# DC27-bottom.net
KiCad netlist of a schematic drawn in EAGLE
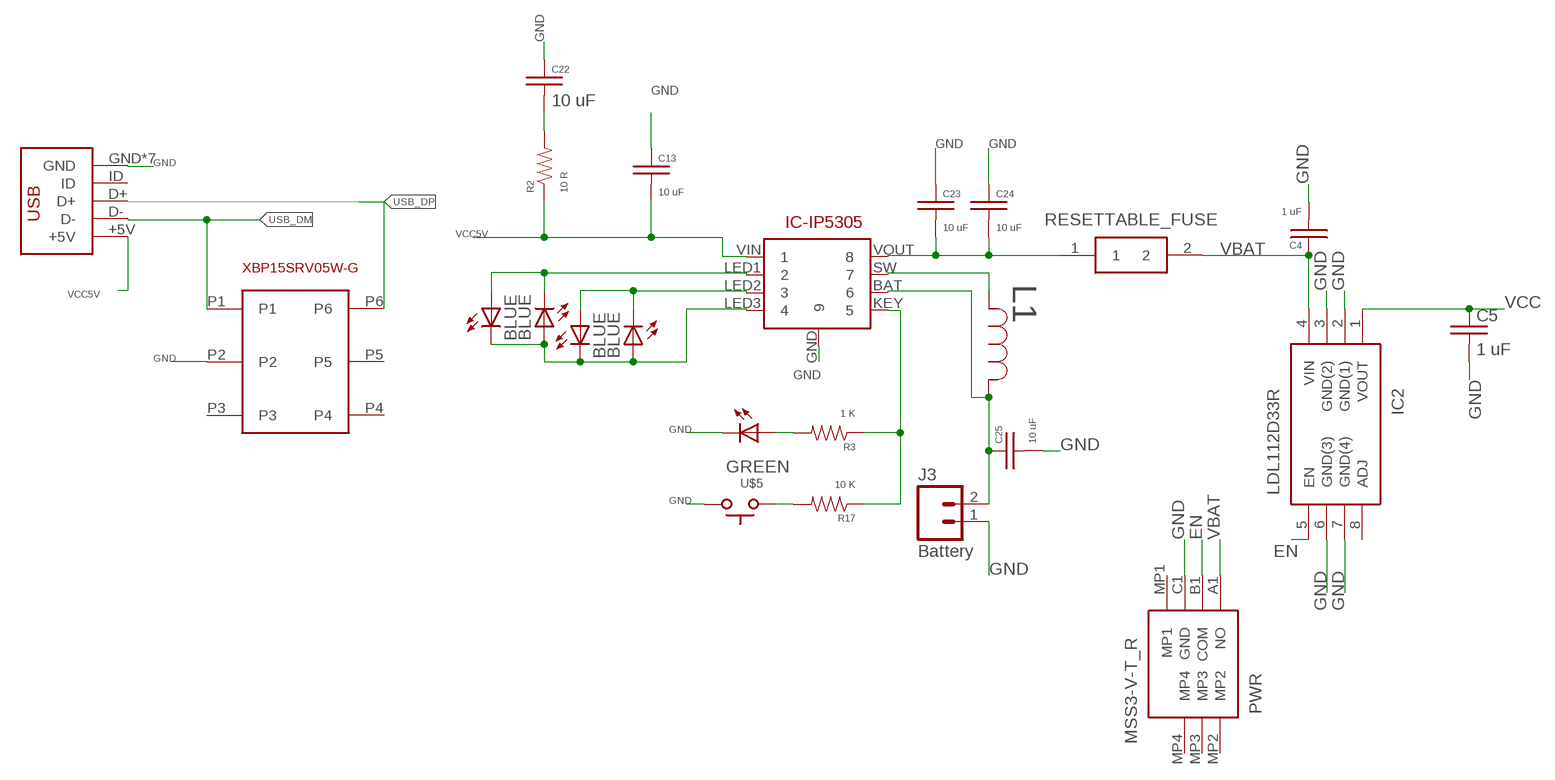
[diagram p0: schematic, sheet 1]
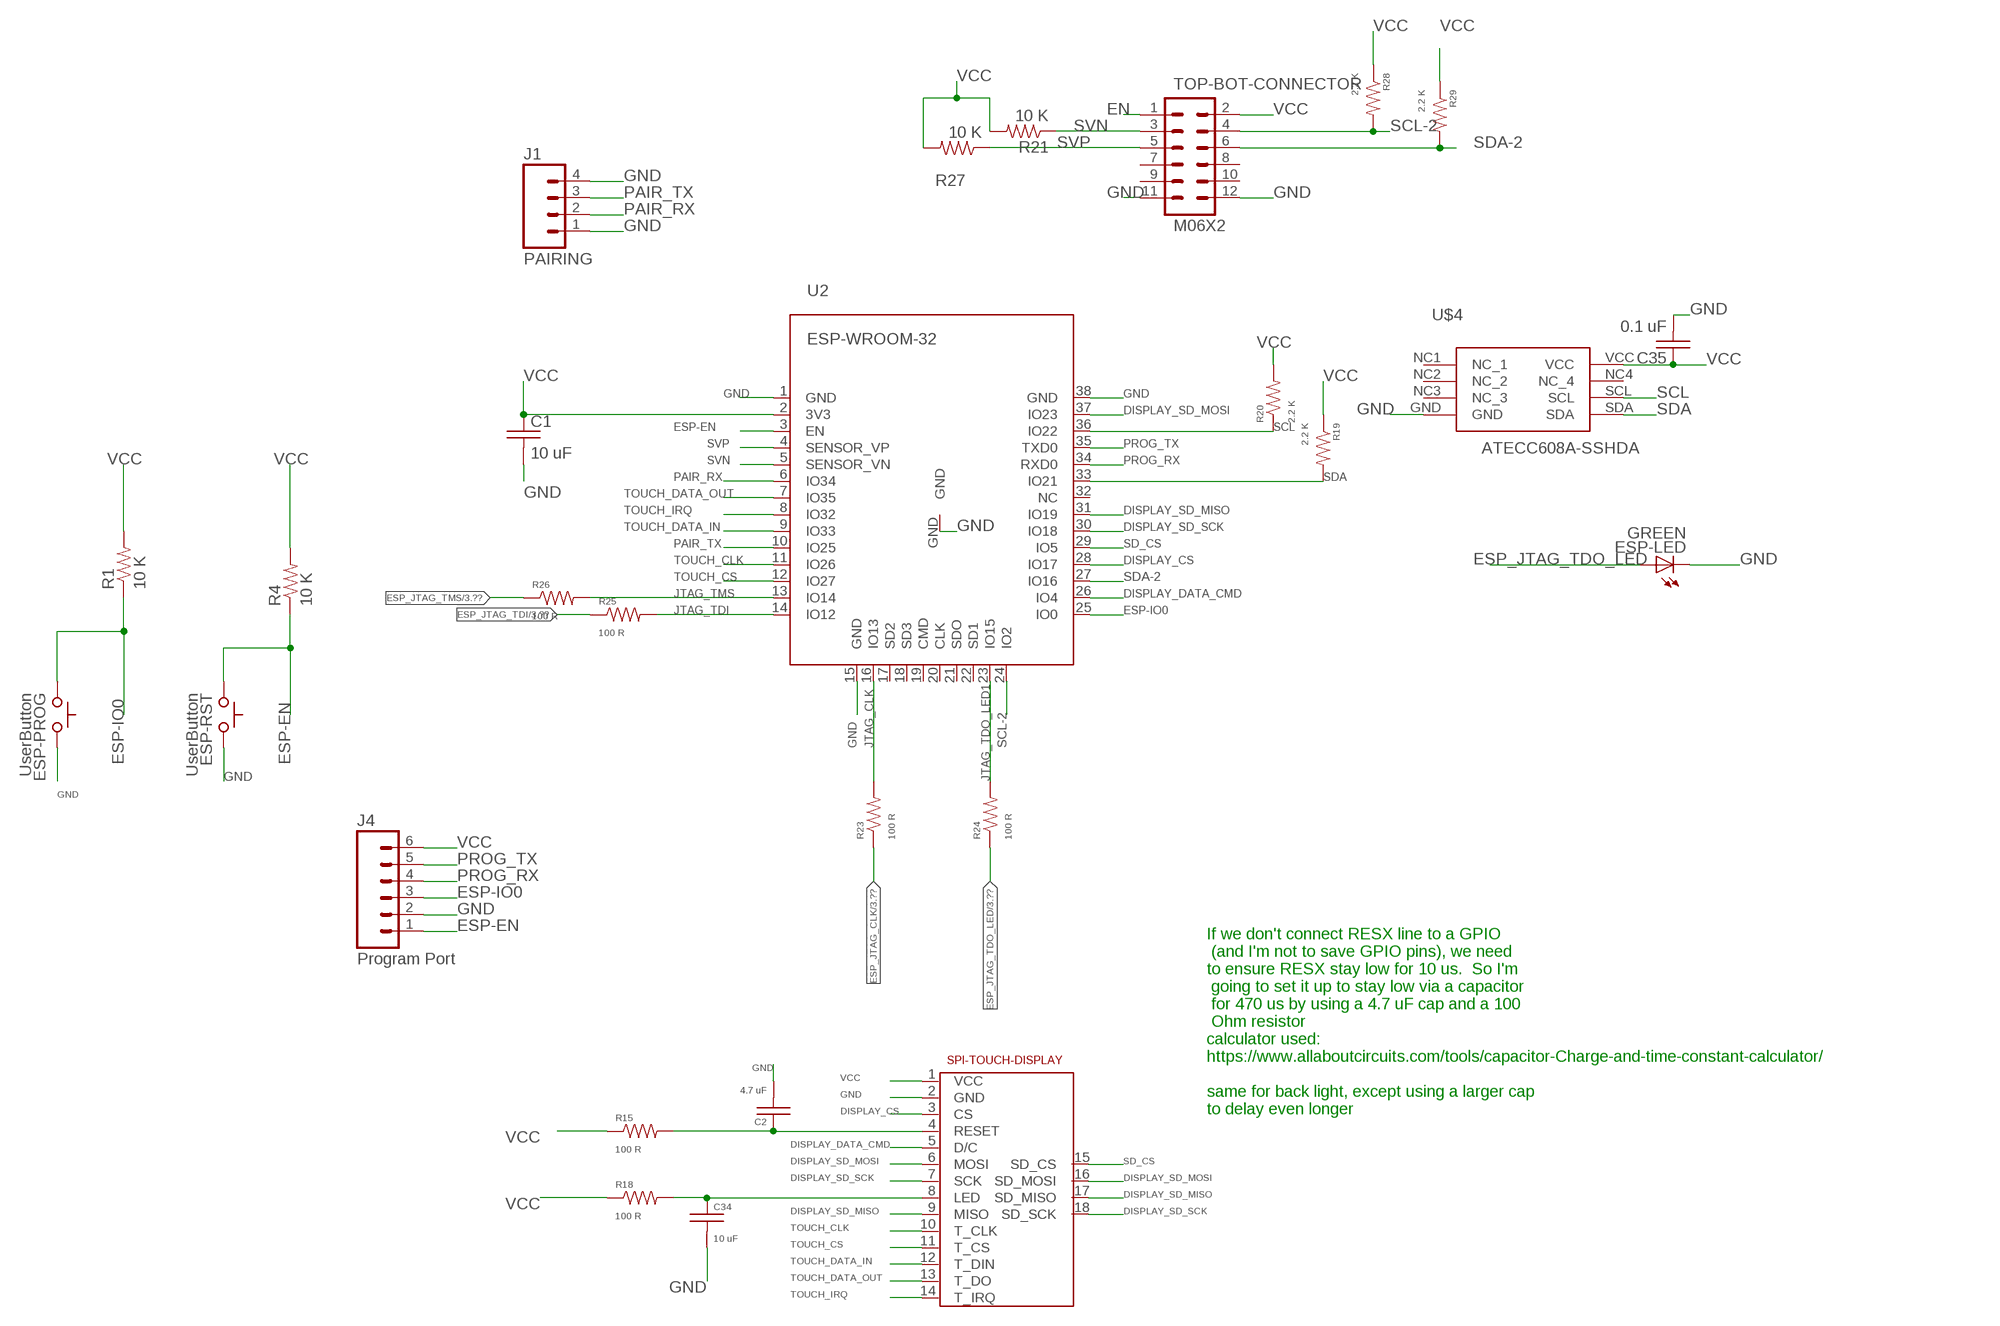
[diagram p1: schematic, sheet 2]
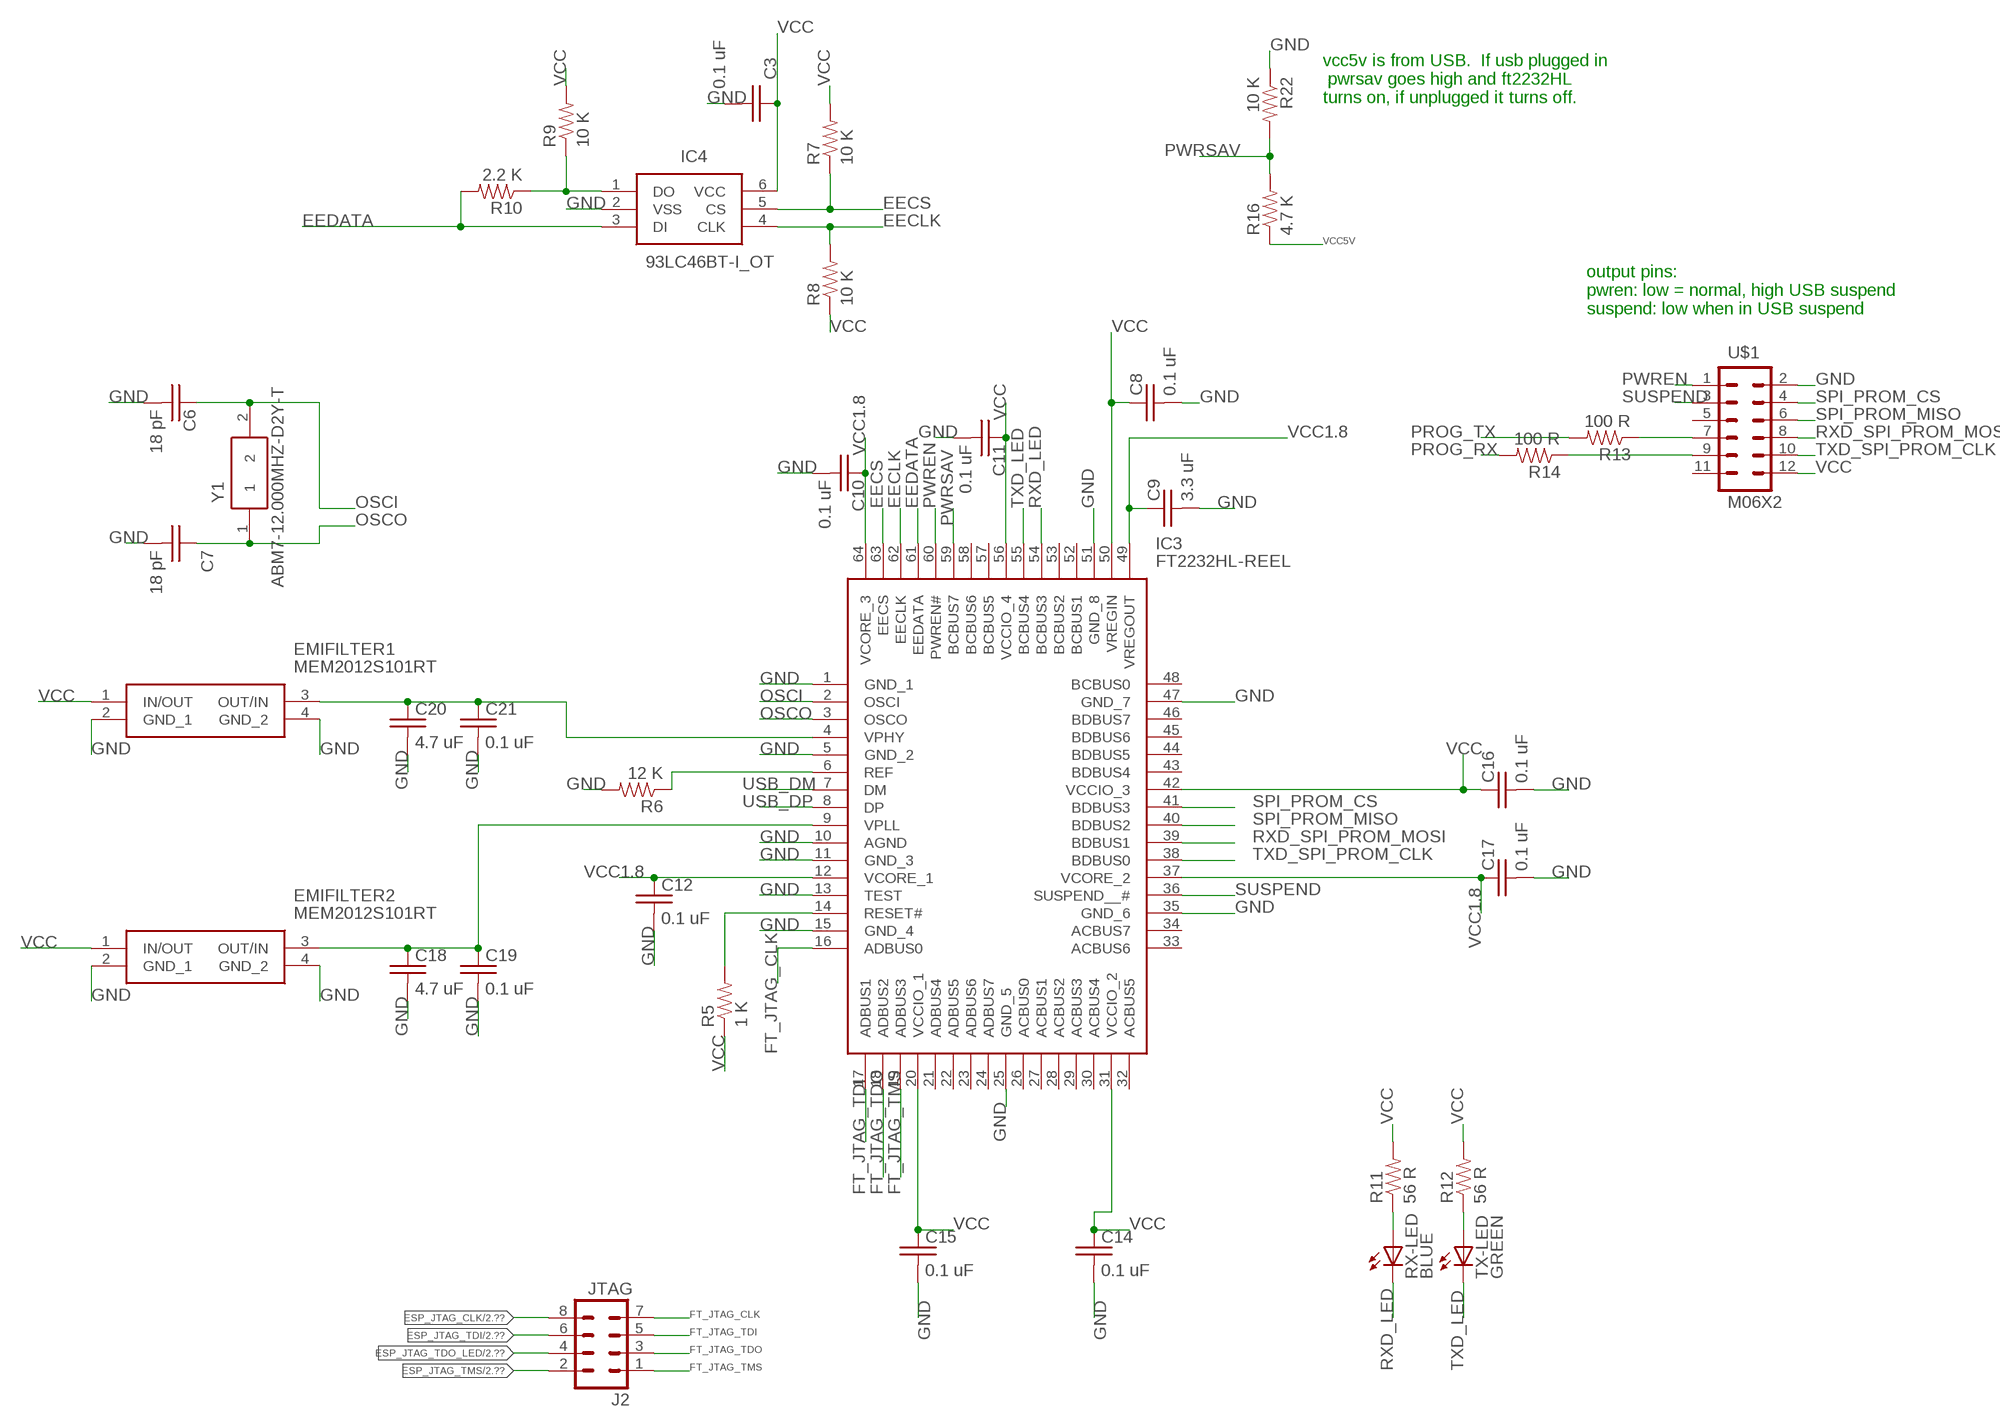
[diagram p2: schematic, sheet 3]
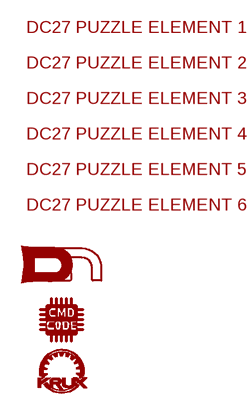
[diagram p3: schematic, sheet 4]

(export (version "E")
  (design (tool "Eeschema 10.0.6"))
  (components
    (comp (ref "C4")
      (value "1 uF")
      (footprint "eagle-import:C0805")
      (libsource (lib "eagle-import") (part "C-USC0805"))
    )
    (comp (ref "C5")
      (value "1 uF")
      (footprint "eagle-import:C0805")
      (libsource (lib "eagle-import") (part "C-USC0805"))
    )
    (comp (ref "C13")
      (value "10 uF")
      (footprint "eagle-import:C0805")
      (libsource (lib "eagle-import") (part "C-USC0805"))
    )
    (comp (ref "C22")
      (value "10 uF")
      (footprint "eagle-import:C0805")
      (libsource (lib "eagle-import") (part "C-USC0805"))
    )
    (comp (ref "C23")
      (value "10 uF")
      (footprint "eagle-import:C0805")
      (libsource (lib "eagle-import") (part "C-USC0805"))
    )
    (comp (ref "C24")
      (value "10 uF")
      (footprint "eagle-import:C0805")
      (libsource (lib "eagle-import") (part "C-USC0805"))
    )
    (comp (ref "C25")
      (value "10 uF")
      (footprint "eagle-import:C0805")
      (libsource (lib "eagle-import") (part "C-USC0805"))
    )
    (comp (ref "CL1")
      (value "BLUE")
      (footprint "eagle-import:LED-1206")
      (libsource (lib "eagle-import") (part "LED1206"))
    )
    (comp (ref "CL2")
      (value "BLUE")
      (footprint "eagle-import:LED-1206")
      (libsource (lib "eagle-import") (part "LED1206"))
    )
    (comp (ref "CL3")
      (value "BLUE")
      (footprint "eagle-import:LED-1206")
      (libsource (lib "eagle-import") (part "LED1206"))
    )
    (comp (ref "CL4")
      (value "BLUE")
      (footprint "eagle-import:LED-1206")
      (libsource (lib "eagle-import") (part "LED1206"))
    )
    (comp (ref "IC-IP5305")
      (value "IP5305ESOP8")
      (footprint "eagle-import:SOIC127P600X165-8")
      (libsource (lib "eagle-import") (part "IP5305ESOP8"))
    )
    (comp (ref "IC2")
      (value "LDL112D33R")
      (footprint "eagle-import:SOIC127P600X175-8N")
      (libsource (lib "eagle-import") (part "LDL112D33R"))
    )
    (comp (ref "J3")
      (value "Battery")
      (footprint "eagle-import:JST-2-PTH")
      (libsource (lib "eagle-import") (part "M02JST-PTH-2"))
    )
    (comp (ref "KEYLED")
      (value "GREEN")
      (footprint "eagle-import:LED-1206")
      (libsource (lib "eagle-import") (part "LED1206"))
    )
    (comp (ref "L1")
      (value "2.2uH")
      (footprint "eagle-import:IND_TAIYO_NRS4018")
      (fields (field (name "MANUFACTURER_PART_NUMBER") "NRS4018T2R2MDGJ"))
      (libsource (lib "eagle-import") (part "NRS4018T2R2MDGJ"))
    )
    (comp (ref "PWR")
      (value "MSS3-V-T_R")
      (footprint "eagle-import:MSS3VTR")
      (fields
        (field (name "MANUFACTURER_PART_NUMBER") "MSS3-V-T/R")
        (field (name "MOUSER_PART_NUMBER") "113-MSS3-V-T/R")
      )
      (libsource (lib "eagle-import") (part "MSS3-V-T_R"))
    )
    (comp (ref "R2")
      (value "10 R")
      (footprint "eagle-import:0805")
      (libsource (lib "eagle-import") (part "passives_RESISTOR0805-RES"))
    )
    (comp (ref "R3")
      (value "1 K")
      (footprint "eagle-import:0805")
      (libsource (lib "eagle-import") (part "passives_RESISTOR0805-RES"))
    )
    (comp (ref "R17")
      (value "10 K")
      (footprint "eagle-import:0805")
      (libsource (lib "eagle-import") (part "passives_RESISTOR0805-RES"))
    )
    (comp (ref "RESETTABLE_FUSE")
      (value "0ZCJ0050FF2G")
      (footprint "eagle-import:FUSC3216X55N")
      (libsource (lib "eagle-import") (part "0ZCJ0050FF2G"))
    )
    (comp (ref "U$2")
      (value "XBP15SRV05W-G")
      (footprint "eagle-import:SOT-26P-XBP15SRV05W-G")
      (fields (field (name "DIGI_KEY_PART_NUMBER") "893-1422-1-ND"))
      (libsource (lib "eagle-import") (part "XBP15SRV05W-G"))
    )
    (comp (ref "U$3")
      (value "DX4R005JJ2DX4R005JJ2")
      (footprint "eagle-import:DX4R005JJ2")
      (libsource (lib "eagle-import") (part "DX4R005JJ2DX4R005JJ2"))
    )
    (comp (ref "U$5")
      (value "SWITCH_TACTILETACTILE-2PIN-NARROW")
      (footprint "eagle-import:TACTILE-2PIN-NARROW")
      (libsource (lib "eagle-import") (part "switches_SWITCH_TACTILETACTILE-2PIN-NARROW"))
    )
    (comp (ref "U$6")
      (value "DC27_PUZZLE_ELEMENT_1")
      (footprint "eagle-import:DC27_PUZZLE_ELEMENT_1")
      (libsource (lib "eagle-import") (part "DC27_PUZZLE_ELEMENT_1"))
    )
    (comp (ref "U$7")
      (value "KRUX_LOGO")
      (footprint "eagle-import:KRUX_LOGO")
      (libsource (lib "eagle-import") (part "KRUX_LOGO"))
    )
    (comp (ref "U$8")
      (value "CMD_C0DE_LOGO")
      (footprint "eagle-import:CMD_C0DE_LOGO")
      (libsource (lib "eagle-import") (part "CMD_C0DE_LOGO"))
    )
    (comp (ref "U$9")
      (value "DN_LOGODC26")
      (footprint "eagle-import:DN_LOGO_DC26")
      (libsource (lib "eagle-import") (part "DN_LOGODC26"))
    )
    (comp (ref "U$11")
      (value "DC27_PUZZLE_ELEMENT_2")
      (footprint "eagle-import:DC27_PUZZLE_ELEMENT_2")
      (libsource (lib "eagle-import") (part "DC27_PUZZLE_ELEMENT_2"))
    )
    (comp (ref "U$12")
      (value "DC27_PUZZLE_ELEMENT_3")
      (footprint "eagle-import:DC27_PUZZLE_ELEMENT_3")
      (libsource (lib "eagle-import") (part "DC27_PUZZLE_ELEMENT_3"))
    )
    (comp (ref "U$13")
      (value "DC27_PUZZLE_ELEMENT_4")
      (footprint "eagle-import:DC27_PUZZLE_ELEMENT_4")
      (libsource (lib "eagle-import") (part "DC27_PUZZLE_ELEMENT_4"))
    )
    (comp (ref "U$14")
      (value "DC27_PUZZLE_ELEMENT_5")
      (footprint "eagle-import:DC27_PUZZLE_ELEMENT_5")
      (libsource (lib "eagle-import") (part "DC27_PUZZLE_ELEMENT_5"))
    )
    (comp (ref "U$15")
      (value "DC27_PUZZLE_ELEMENT_6")
      (footprint "eagle-import:DC27_PUZZLE_ELEMENT_6")
      (libsource (lib "eagle-import") (part "DC27_PUZZLE_ELEMENT_6"))
    )
    (comp (ref "C3")
      (value "0.1 uF")
      (footprint "eagle-import:C0805")
      (libsource (lib "eagle-import") (part "C-USC0805"))
    )
    (comp (ref "C6")
      (value "18 pF")
      (footprint "eagle-import:C0805")
      (libsource (lib "eagle-import") (part "C-USC0805"))
    )
    (comp (ref "C7")
      (value "18 pF")
      (footprint "eagle-import:C0805")
      (libsource (lib "eagle-import") (part "C-USC0805"))
    )
    (comp (ref "C8")
      (value "0.1 uF")
      (footprint "eagle-import:C0805")
      (libsource (lib "eagle-import") (part "C-USC0805"))
    )
    (comp (ref "C9")
      (value "3.3 uF")
      (footprint "eagle-import:C0805")
      (libsource (lib "eagle-import") (part "C-USC0805"))
    )
    (comp (ref "C10")
      (value "0.1 uF")
      (footprint "eagle-import:C0805")
      (libsource (lib "eagle-import") (part "C-USC0805"))
    )
    (comp (ref "C11")
      (value "0.1 uF")
      (footprint "eagle-import:C0805")
      (libsource (lib "eagle-import") (part "C-USC0805"))
    )
    (comp (ref "C12")
      (value "0.1 uF")
      (footprint "eagle-import:C0805")
      (libsource (lib "eagle-import") (part "C-USC0805"))
    )
    (comp (ref "C14")
      (value "0.1 uF")
      (footprint "eagle-import:C0805")
      (libsource (lib "eagle-import") (part "C-USC0805"))
    )
    (comp (ref "C15")
      (value "0.1 uF")
      (footprint "eagle-import:C0805")
      (libsource (lib "eagle-import") (part "C-USC0805"))
    )
    (comp (ref "C16")
      (value "0.1 uF")
      (footprint "eagle-import:C0805")
      (libsource (lib "eagle-import") (part "C-USC0805"))
    )
    (comp (ref "C17")
      (value "0.1 uF")
      (footprint "eagle-import:C0805")
      (libsource (lib "eagle-import") (part "C-USC0805"))
    )
    (comp (ref "C18")
      (value "4.7 uF")
      (footprint "eagle-import:C0805")
      (libsource (lib "eagle-import") (part "C-USC0805"))
    )
    (comp (ref "C19")
      (value "0.1 uF")
      (footprint "eagle-import:C0805")
      (libsource (lib "eagle-import") (part "C-USC0805"))
    )
    (comp (ref "C20")
      (value "4.7 uF")
      (footprint "eagle-import:C0805")
      (libsource (lib "eagle-import") (part "C-USC0805"))
    )
    (comp (ref "C21")
      (value "0.1 uF")
      (footprint "eagle-import:C0805")
      (libsource (lib "eagle-import") (part "C-USC0805"))
    )
    (comp (ref "EMIFILTER1")
      (value "MEM2012S101RT")
      (footprint "eagle-import:MEM2012S101RT")
      (libsource (lib "eagle-import") (part "MEM2012S101RT"))
    )
    (comp (ref "EMIFILTER2")
      (value "MEM2012S101RT")
      (footprint "eagle-import:MEM2012S101RT")
      (libsource (lib "eagle-import") (part "MEM2012S101RT"))
    )
    (comp (ref "IC3")
      (value "FT2232HL-REEL")
      (footprint "eagle-import:QFP50P1200X1200X160-64N")
      (fields (field (name "MOUSER_PART_NUMBER") "895-FT2232HL"))
      (libsource (lib "eagle-import") (part "FT2232HL-REEL"))
    )
    (comp (ref "IC4")
      (value "93LC46BT-I_OT")
      (footprint "eagle-import:SOT95P270X145-6N")
      (fields
        (field (name "MANUFACTURER_PART_NUMBER") "93LC46BT-I/OT")
        (field (name "MOUSER_PART_NUMBER") "579-93LC46BT-I/OT")
      )
      (libsource (lib "eagle-import") (part "93LC46BT-I_OT"))
    )
    (comp (ref "J2")
      (value "JTAG")
      (footprint "eagle-import:2X4")
      (libsource (lib "eagle-import") (part "M04X2"))
    )
    (comp (ref "R5")
      (value "1 K")
      (footprint "eagle-import:0805")
      (libsource (lib "eagle-import") (part "passives_RESISTOR0805-RES"))
    )
    (comp (ref "R6")
      (value "12 K")
      (footprint "eagle-import:0805")
      (libsource (lib "eagle-import") (part "passives_RESISTOR0805-RES"))
    )
    (comp (ref "R7")
      (value "10 K")
      (footprint "eagle-import:0805")
      (libsource (lib "eagle-import") (part "passives_RESISTOR0805-RES"))
    )
    (comp (ref "R8")
      (value "10 K")
      (footprint "eagle-import:0805")
      (libsource (lib "eagle-import") (part "passives_RESISTOR0805-RES"))
    )
    (comp (ref "R9")
      (value "10 K")
      (footprint "eagle-import:0805")
      (libsource (lib "eagle-import") (part "passives_RESISTOR0805-RES"))
    )
    (comp (ref "R10")
      (value "2.2 K")
      (footprint "eagle-import:0805")
      (libsource (lib "eagle-import") (part "passives_RESISTOR0805-RES"))
    )
    (comp (ref "R11")
      (value "56 R")
      (footprint "eagle-import:0805")
      (libsource (lib "eagle-import") (part "passives_RESISTOR0805-RES"))
    )
    (comp (ref "R12")
      (value "56 R")
      (footprint "eagle-import:0805")
      (libsource (lib "eagle-import") (part "passives_RESISTOR0805-RES"))
    )
    (comp (ref "R13")
      (value "100 R")
      (footprint "eagle-import:0805")
      (libsource (lib "eagle-import") (part "passives_RESISTOR0805-RES"))
    )
    (comp (ref "R14")
      (value "100 R")
      (footprint "eagle-import:0805")
      (libsource (lib "eagle-import") (part "passives_RESISTOR0805-RES"))
    )
    (comp (ref "R16")
      (value "4.7 K")
      (footprint "eagle-import:0805")
      (libsource (lib "eagle-import") (part "passives_RESISTOR0805-RES"))
    )
    (comp (ref "R22")
      (value "10 K")
      (footprint "eagle-import:0805")
      (libsource (lib "eagle-import") (part "passives_RESISTOR0805-RES"))
    )
    (comp (ref "RX-LED")
      (value "BLUE")
      (footprint "eagle-import:LED-1206")
      (libsource (lib "eagle-import") (part "LED1206"))
    )
    (comp (ref "TX-LED")
      (value "GREEN")
      (footprint "eagle-import:LED-1206")
      (libsource (lib "eagle-import") (part "LED1206"))
    )
    (comp (ref "U$1")
      (value "M06X2")
      (footprint "eagle-import:2X6")
      (libsource (lib "eagle-import") (part "M06X2"))
    )
    (comp (ref "Y1")
      (value "ABM7-12.000MHZ-D2Y-T")
      (footprint "eagle-import:ABM7")
      (fields
        (field (name "MOUSER_PART_NUMBER") "815-ABM7-12-D2Y-T")
        (field (name "RS_PART_NUMBER") "1710625P")
      )
      (libsource (lib "eagle-import") (part "ABM7-12.000MHZ-D2Y-T"))
    )
    (comp (ref "C1")
      (value "10 uF")
      (footprint "eagle-import:C0805")
      (libsource (lib "eagle-import") (part "C-USC0805"))
    )
    (comp (ref "C2")
      (value "4.7 uF")
      (footprint "eagle-import:C0805")
      (libsource (lib "eagle-import") (part "C-USC0805"))
    )
    (comp (ref "C34")
      (value "10 uF")
      (footprint "eagle-import:C0805")
      (libsource (lib "eagle-import") (part "C-USC0805"))
    )
    (comp (ref "C35")
      (value "0.1 uF")
      (footprint "eagle-import:C0805")
      (libsource (lib "eagle-import") (part "C-USC0805"))
    )
    (comp (ref "ESP-LED")
      (value "GREEN")
      (footprint "eagle-import:LED-1206")
      (libsource (lib "eagle-import") (part "LED1206"))
    )
    (comp (ref "ESP-PROG")
      (value "UserButton")
      (footprint "eagle-import:TACTILE-2PIN-NARROW")
      (libsource (lib "eagle-import") (part "SWITCH_TACTILETACTILE-2PIN-NARROW"))
    )
    (comp (ref "ESP-RST")
      (value "UserButton")
      (footprint "eagle-import:TACTILE-2PIN-NARROW")
      (libsource (lib "eagle-import") (part "SWITCH_TACTILETACTILE-2PIN-NARROW"))
    )
    (comp (ref "J1")
      (value "PAIRING")
      (footprint "eagle-import:1X04")
      (libsource (lib "eagle-import") (part "M04PTH"))
    )
    (comp (ref "J4")
      (value "Program Port")
      (footprint "eagle-import:1X06-SMD-POGO")
      (libsource (lib "eagle-import") (part "M06POGO-PIN"))
    )
    (comp (ref "R1")
      (value "10 K")
      (footprint "eagle-import:0805")
      (libsource (lib "eagle-import") (part "RESISTOR0805-RES"))
    )
    (comp (ref "R4")
      (value "10 K")
      (footprint "eagle-import:0805")
      (libsource (lib "eagle-import") (part "RESISTOR0805-RES"))
    )
    (comp (ref "R15")
      (value "100 R")
      (footprint "eagle-import:0805")
      (libsource (lib "eagle-import") (part "RESISTOR0805-RES"))
    )
    (comp (ref "R18")
      (value "100 R")
      (footprint "eagle-import:0805")
      (libsource (lib "eagle-import") (part "RESISTOR0805-RES"))
    )
    (comp (ref "R19")
      (value "2.2 K")
      (footprint "eagle-import:0805")
      (libsource (lib "eagle-import") (part "RESISTOR0805-RES"))
    )
    (comp (ref "R20")
      (value "2.2 K")
      (footprint "eagle-import:0805")
      (libsource (lib "eagle-import") (part "RESISTOR0805-RES"))
    )
    (comp (ref "R21")
      (value "10 K")
      (footprint "eagle-import:0805")
      (libsource (lib "eagle-import") (part "RESISTOR0805-RES"))
    )
    (comp (ref "R23")
      (value "100 R")
      (footprint "eagle-import:0805")
      (libsource (lib "eagle-import") (part "RESISTOR0805-RES"))
    )
    (comp (ref "R24")
      (value "100 R")
      (footprint "eagle-import:0805")
      (libsource (lib "eagle-import") (part "RESISTOR0805-RES"))
    )
    (comp (ref "R25")
      (value "100 R")
      (footprint "eagle-import:0805")
      (libsource (lib "eagle-import") (part "RESISTOR0805-RES"))
    )
    (comp (ref "R26")
      (value "100 R")
      (footprint "eagle-import:0805")
      (libsource (lib "eagle-import") (part "RESISTOR0805-RES"))
    )
    (comp (ref "R27")
      (value "10 K")
      (footprint "eagle-import:0805")
      (libsource (lib "eagle-import") (part "RESISTOR0805-RES"))
    )
    (comp (ref "R28")
      (value "2.2 K")
      (footprint "eagle-import:0805")
      (libsource (lib "eagle-import") (part "RESISTOR0805-RES"))
    )
    (comp (ref "R29")
      (value "2.2 K")
      (footprint "eagle-import:0805")
      (libsource (lib "eagle-import") (part "RESISTOR0805-RES"))
    )
    (comp (ref "TOP-BOT-CONNECTOR")
      (value "M06X2")
      (footprint "eagle-import:2X6")
      (libsource (lib "eagle-import") (part "M06X2"))
    )
    (comp (ref "U$4")
      (value "ATECC608A-SSHDA")
      (footprint "eagle-import:8-SOIC")
      (libsource (lib "eagle-import") (part "ATECC608A-SSHDA"))
    )
    (comp (ref "U$10")
      (value "2.4-SPI-TFT-TOUCH-SSD-MODULE")
      (footprint "eagle-import:2.4-SPI-TFT-TOUCH-SSD-MODULE")
      (libsource (lib "eagle-import") (part "2.4-SPI-TFT-TOUCH-SSD-MODULE"))
    )
    (comp (ref "U2")
      (value "ESP-WROOM-32")
      (footprint "eagle-import:ESP-WROOM-32")
      (libsource (lib "eagle-import") (part "ESP-WROOM-32"))
    )
  )
  (nets
    (net (code "1") (name "DISPLAY_CS") (class "Default")
      (node (ref "U$10") (pin "3") (pinfunction "CS_3") (pintype "bidirectional"))
      (node (ref "U2") (pin "28") (pinfunction "IO17_28") (pintype "bidirectional"))
    )
    (net (code "2") (name "DISPLAY_DATA_CMD") (class "Default")
      (node (ref "U$10") (pin "5") (pinfunction "D/C_5") (pintype "bidirectional"))
      (node (ref "U2") (pin "26") (pinfunction "IO4_26") (pintype "bidirectional"))
    )
    (net (code "3") (name "DISPLAY_SD_MISO") (class "Default")
      (node (ref "U$10") (pin "17") (pinfunction "SD_MISO_17") (pintype "bidirectional"))
      (node (ref "U$10") (pin "9") (pinfunction "MISO_9") (pintype "bidirectional"))
      (node (ref "U2") (pin "31") (pinfunction "IO19_31") (pintype "bidirectional"))
    )
    (net (code "4") (name "DISPLAY_SD_MOSI") (class "Default")
      (node (ref "U$10") (pin "16") (pinfunction "SD_MOSI_16") (pintype "bidirectional"))
      (node (ref "U$10") (pin "6") (pinfunction "MOSI_6") (pintype "bidirectional"))
      (node (ref "U2") (pin "37") (pinfunction "IO23_37") (pintype "bidirectional"))
    )
    (net (code "5") (name "DISPLAY_SD_SCK") (class "Default")
      (node (ref "U$10") (pin "18") (pinfunction "SD_SCK_18") (pintype "bidirectional"))
      (node (ref "U$10") (pin "7") (pinfunction "SCK_7") (pintype "bidirectional"))
      (node (ref "U2") (pin "30") (pinfunction "IO18_30") (pintype "bidirectional"))
    )
    (net (code "6") (name "EECLK") (class "Default")
      (node (ref "IC3") (pin "62") (pinfunction "EECLK_62") (pintype "bidirectional"))
      (node (ref "IC4") (pin "4") (pinfunction "CLK_4") (pintype "input"))
      (node (ref "R8") (pin "2") (pinfunction "2_2") (pintype "passive"))
    )
    (net (code "7") (name "EECS") (class "Default")
      (node (ref "IC3") (pin "63") (pinfunction "EECS_63") (pintype "bidirectional"))
      (node (ref "IC4") (pin "5") (pinfunction "CS_5") (pintype "input"))
      (node (ref "R7") (pin "1") (pinfunction "1_1") (pintype "passive"))
    )
    (net (code "8") (name "EEDATA") (class "Default")
      (node (ref "IC3") (pin "61") (pinfunction "EEDATA_61") (pintype "bidirectional"))
      (node (ref "IC4") (pin "3") (pinfunction "DI_3") (pintype "bidirectional"))
      (node (ref "R10") (pin "2") (pinfunction "2_2") (pintype "passive"))
    )
    (net (code "9") (name "EN") (class "Default")
      (node (ref "IC2") (pin "5") (pinfunction "EN_5") (pintype "bidirectional"))
      (node (ref "PWR") (pin "B1") (pinfunction "COM_B1") (pintype "bidirectional"))
      (node (ref "TOP-BOT-CONNECTOR") (pin "1") (pinfunction "1_1") (pintype "passive"))
    )
    (net (code "10") (name "ESP-EN") (class "Default")
      (node (ref "ESP-RST") (pin "P$2") (pinfunction "C_P$2") (pintype "passive"))
      (node (ref "J4") (pin "1") (pinfunction "1_1") (pintype "passive"))
      (node (ref "R4") (pin "1") (pinfunction "1_1") (pintype "passive"))
      (node (ref "U2") (pin "3") (pinfunction "EN_3") (pintype "bidirectional"))
    )
    (net (code "11") (name "ESP-IO0") (class "Default")
      (node (ref "ESP-PROG") (pin "P$2") (pinfunction "C_P$2") (pintype "passive"))
      (node (ref "J4") (pin "3") (pinfunction "3_3") (pintype "passive"))
      (node (ref "R1") (pin "1") (pinfunction "1_1") (pintype "passive"))
      (node (ref "U2") (pin "25") (pinfunction "IO0_25") (pintype "bidirectional"))
    )
    (net (code "12") (name "ESP_JTAG_CLK") (class "Default")
      (node (ref "J2") (pin "8") (pinfunction "8_8") (pintype "passive"))
      (node (ref "R23") (pin "1") (pinfunction "1_1") (pintype "passive"))
    )
    (net (code "13") (name "ESP_JTAG_TDI") (class "Default")
      (node (ref "J2") (pin "6") (pinfunction "6_6") (pintype "passive"))
      (node (ref "R25") (pin "1") (pinfunction "1_1") (pintype "passive"))
    )
    (net (code "14") (name "ESP_JTAG_TDO_LED") (class "Default")
      (node (ref "ESP-LED") (pin "A") (pinfunction "A_A") (pintype "input"))
      (node (ref "J2") (pin "4") (pinfunction "4_4") (pintype "passive"))
      (node (ref "R24") (pin "1") (pinfunction "1_1") (pintype "passive"))
    )
    (net (code "15") (name "ESP_JTAG_TMS") (class "Default")
      (node (ref "J2") (pin "2") (pinfunction "2_2") (pintype "passive"))
      (node (ref "R26") (pin "1") (pinfunction "1_1") (pintype "passive"))
    )
    (net (code "16") (name "FT_JTAG_CLK") (class "Default")
      (node (ref "IC3") (pin "16") (pinfunction "ADBUS0_16") (pintype "bidirectional"))
      (node (ref "J2") (pin "7") (pinfunction "7_7") (pintype "passive"))
    )
    (net (code "17") (name "FT_JTAG_TDI") (class "Default")
      (node (ref "IC3") (pin "17") (pinfunction "ADBUS1_17") (pintype "bidirectional"))
      (node (ref "J2") (pin "5") (pinfunction "5_5") (pintype "passive"))
    )
    (net (code "18") (name "FT_JTAG_TDO") (class "Default")
      (node (ref "IC3") (pin "18") (pinfunction "ADBUS2_18") (pintype "bidirectional"))
      (node (ref "J2") (pin "3") (pinfunction "3_3") (pintype "passive"))
    )
    (net (code "19") (name "FT_JTAG_TMS") (class "Default")
      (node (ref "IC3") (pin "19") (pinfunction "ADBUS3_19") (pintype "bidirectional"))
      (node (ref "J2") (pin "1") (pinfunction "1_1") (pintype "passive"))
    )
    (net (code "20") (name "GND") (class "Default")
      (node (ref "C1") (pin "2") (pinfunction "2_2") (pintype "passive"))
      (node (ref "C10") (pin "2") (pinfunction "2_2") (pintype "passive"))
      (node (ref "C11") (pin "2") (pinfunction "2_2") (pintype "passive"))
      (node (ref "C12") (pin "2") (pinfunction "2_2") (pintype "passive"))
      (node (ref "C13") (pin "1") (pinfunction "1_1") (pintype "passive"))
      (node (ref "C14") (pin "2") (pinfunction "2_2") (pintype "passive"))
      (node (ref "C15") (pin "2") (pinfunction "2_2") (pintype "passive"))
      (node (ref "C16") (pin "2") (pinfunction "2_2") (pintype "passive"))
      (node (ref "C17") (pin "2") (pinfunction "2_2") (pintype "passive"))
      (node (ref "C18") (pin "2") (pinfunction "2_2") (pintype "passive"))
      (node (ref "C19") (pin "2") (pinfunction "2_2") (pintype "passive"))
      (node (ref "C2") (pin "2") (pinfunction "2_2") (pintype "passive"))
      (node (ref "C20") (pin "2") (pinfunction "2_2") (pintype "passive"))
      (node (ref "C21") (pin "2") (pinfunction "2_2") (pintype "passive"))
      (node (ref "C22") (pin "1") (pinfunction "1_1") (pintype "passive"))
      (node (ref "C23") (pin "1") (pinfunction "1_1") (pintype "passive"))
      (node (ref "C24") (pin "1") (pinfunction "1_1") (pintype "passive"))
      (node (ref "C25") (pin "2") (pinfunction "2_2") (pintype "passive"))
      (node (ref "C3") (pin "2") (pinfunction "2_2") (pintype "passive"))
      (node (ref "C34") (pin "2") (pinfunction "2_2") (pintype "passive"))
      (node (ref "C35") (pin "2") (pinfunction "2_2") (pintype "passive"))
      (node (ref "C4") (pin "2") (pinfunction "2_2") (pintype "passive"))
      (node (ref "C5") (pin "2") (pinfunction "2_2") (pintype "passive"))
      (node (ref "C6") (pin "2") (pinfunction "2_2") (pintype "passive"))
      (node (ref "C7") (pin "2") (pinfunction "2_2") (pintype "passive"))
      (node (ref "C8") (pin "2") (pinfunction "2_2") (pintype "passive"))
      (node (ref "C9") (pin "2") (pinfunction "2_2") (pintype "passive"))
      (node (ref "EMIFILTER1") (pin "2") (pinfunction "GND_1_2") (pintype "bidirectional"))
      (node (ref "EMIFILTER1") (pin "4") (pinfunction "GND_2_4") (pintype "bidirectional"))
      (node (ref "EMIFILTER2") (pin "2") (pinfunction "GND_1_2") (pintype "bidirectional"))
      (node (ref "EMIFILTER2") (pin "4") (pinfunction "GND_2_4") (pintype "bidirectional"))
      (node (ref "ESP-LED") (pin "C") (pinfunction "C_C") (pintype "output"))
      (node (ref "ESP-PROG") (pin "P$1") (pinfunction "A_P$1") (pintype "passive"))
      (node (ref "ESP-RST") (pin "P$1") (pinfunction "A_P$1") (pintype "passive"))
      (node (ref "IC-IP5305") (pin "GND") (pinfunction "9_GND") (pintype "bidirectional"))
      (node (ref "IC2") (pin "2") (pinfunction "GND(1)_2") (pintype "bidirectional"))
      (node (ref "IC2") (pin "3") (pinfunction "GND(2)_3") (pintype "bidirectional"))
      (node (ref "IC2") (pin "6") (pinfunction "GND(3)_6") (pintype "bidirectional"))
      (node (ref "IC2") (pin "7") (pinfunction "GND(4)_7") (pintype "bidirectional"))
      (node (ref "IC3") (pin "1") (pinfunction "GND_1_1") (pintype "bidirectional"))
      (node (ref "IC3") (pin "10") (pinfunction "AGND_10") (pintype "bidirectional"))
      (node (ref "IC3") (pin "11") (pinfunction "GND_3_11") (pintype "bidirectional"))
      (node (ref "IC3") (pin "13") (pinfunction "TEST_13") (pintype "bidirectional"))
      (node (ref "IC3") (pin "15") (pinfunction "GND_4_15") (pintype "bidirectional"))
      (node (ref "IC3") (pin "25") (pinfunction "GND_5_25") (pintype "bidirectional"))
      (node (ref "IC3") (pin "35") (pinfunction "GND_6_35") (pintype "bidirectional"))
      (node (ref "IC3") (pin "47") (pinfunction "GND_7_47") (pintype "bidirectional"))
      (node (ref "IC3") (pin "5") (pinfunction "GND_2_5") (pintype "bidirectional"))
      (node (ref "IC3") (pin "51") (pinfunction "GND_8_51") (pintype "bidirectional"))
      (node (ref "IC4") (pin "2") (pinfunction "VSS_2") (pintype "power_in"))
      (node (ref "J1") (pin "1") (pinfunction "1_1") (pintype "passive"))
      (node (ref "J1") (pin "4") (pinfunction "4_4") (pintype "passive"))
      (node (ref "J3") (pin "1") (pinfunction "1_1") (pintype "passive"))
      (node (ref "J4") (pin "2") (pinfunction "2_2") (pintype "passive"))
      (node (ref "KEYLED") (pin "C") (pinfunction "C_C") (pintype "output"))
      (node (ref "PWR") (pin "C1") (pinfunction "GND_C1") (pintype "bidirectional"))
      (node (ref "R22") (pin "1") (pinfunction "1_1") (pintype "passive"))
      (node (ref "R6") (pin "2") (pinfunction "2_2") (pintype "passive"))
      (node (ref "TOP-BOT-CONNECTOR") (pin "11") (pinfunction "11_11") (pintype "passive"))
      (node (ref "TOP-BOT-CONNECTOR") (pin "12") (pinfunction "12_12") (pintype "passive"))
      (node (ref "U$1") (pin "2") (pinfunction "2_2") (pintype "passive"))
      (node (ref "U$10") (pin "2") (pinfunction "GND_2") (pintype "power_in"))
      (node (ref "U$2") (pin "P2") (pinfunction "P2_P2") (pintype "bidirectional"))
      (node (ref "U$3") (pin "GND") (pinfunction "GND_GND") (pintype "bidirectional"))
      (node (ref "U$3") (pin "P$10") (pinfunction "GND_P$10") (pintype "bidirectional"))
      (node (ref "U$3") (pin "P$11") (pinfunction "GND_P$11") (pintype "bidirectional"))
      (node (ref "U$3") (pin "P$6") (pinfunction "GND_P$6") (pintype "bidirectional"))
      (node (ref "U$3") (pin "P$7") (pinfunction "GND_P$7") (pintype "bidirectional"))
      (node (ref "U$3") (pin "P$8") (pinfunction "GND_P$8") (pintype "bidirectional"))
      (node (ref "U$3") (pin "P$9") (pinfunction "GND_P$9") (pintype "bidirectional"))
      (node (ref "U$4") (pin "GND") (pinfunction "GND_GND") (pintype "power_in"))
      (node (ref "U$5") (pin "P$1") (pinfunction "A_P$1") (pintype "passive"))
      (node (ref "U2") (pin "1") (pinfunction "GND_1") (pintype "bidirectional"))
      (node (ref "U2") (pin "15") (pinfunction "GND_15") (pintype "bidirectional"))
      (node (ref "U2") (pin "38") (pinfunction "GND_38") (pintype "bidirectional"))
      (node (ref "U2") (pin "GND") (pinfunction "GND_GND") (pintype "bidirectional"))
    )
    (net (code "21") (name "JTAG_CLK") (class "Default")
      (node (ref "R23") (pin "2") (pinfunction "2_2") (pintype "passive"))
      (node (ref "U2") (pin "16") (pinfunction "IO13_16") (pintype "bidirectional"))
    )
    (net (code "22") (name "JTAG_TDI") (class "Default")
      (node (ref "R25") (pin "2") (pinfunction "2_2") (pintype "passive"))
      (node (ref "U2") (pin "14") (pinfunction "IO12_14") (pintype "bidirectional"))
    )
    (net (code "23") (name "JTAG_TDO_LED1") (class "Default")
      (node (ref "R24") (pin "2") (pinfunction "2_2") (pintype "passive"))
      (node (ref "U2") (pin "23") (pinfunction "IO15_23") (pintype "bidirectional"))
    )
    (net (code "24") (name "JTAG_TMS") (class "Default")
      (node (ref "R26") (pin "2") (pinfunction "2_2") (pintype "passive"))
      (node (ref "U2") (pin "13") (pinfunction "IO14_13") (pintype "bidirectional"))
    )
    (net (code "25") (name "Net-(C22-Pad2)") (class "Default")
      (node (ref "C22") (pin "2") (pinfunction "2_2") (pintype "passive"))
      (node (ref "R2") (pin "2") (pinfunction "2_2") (pintype "passive"))
    )
    (net (code "26") (name "Net-(EMIFILTER1-OUT{slash}IN)") (class "Default")
      (node (ref "C20") (pin "1") (pinfunction "1_1") (pintype "passive"))
      (node (ref "C21") (pin "1") (pinfunction "1_1") (pintype "passive"))
      (node (ref "EMIFILTER1") (pin "3") (pinfunction "OUT/IN_3") (pintype "bidirectional"))
      (node (ref "IC3") (pin "4") (pinfunction "VPHY_4") (pintype "bidirectional"))
    )
    (net (code "27") (name "Net-(EMIFILTER2-OUT{slash}IN)") (class "Default")
      (node (ref "C18") (pin "1") (pinfunction "1_1") (pintype "passive"))
      (node (ref "C19") (pin "1") (pinfunction "1_1") (pintype "passive"))
      (node (ref "EMIFILTER2") (pin "3") (pinfunction "OUT/IN_3") (pintype "bidirectional"))
      (node (ref "IC3") (pin "9") (pinfunction "VPLL_9") (pintype "bidirectional"))
    )
    (net (code "28") (name "Net-(IC-IP5305-2)") (class "Default")
      (node (ref "CL1") (pin "A") (pinfunction "A_A") (pintype "input"))
      (node (ref "CL2") (pin "C") (pinfunction "C_C") (pintype "output"))
      (node (ref "IC-IP5305") (pin "LED1") (pinfunction "2_LED1") (pintype "output"))
    )
    (net (code "29") (name "Net-(IC-IP5305-3)") (class "Default")
      (node (ref "CL3") (pin "A") (pinfunction "A_A") (pintype "input"))
      (node (ref "CL4") (pin "C") (pinfunction "C_C") (pintype "output"))
      (node (ref "IC-IP5305") (pin "LED2") (pinfunction "3_LED2") (pintype "output"))
    )
    (net (code "30") (name "Net-(IC-IP5305-4)") (class "Default")
      (node (ref "CL1") (pin "C") (pinfunction "C_C") (pintype "output"))
      (node (ref "CL2") (pin "A") (pinfunction "A_A") (pintype "input"))
      (node (ref "CL3") (pin "C") (pinfunction "C_C") (pintype "output"))
      (node (ref "CL4") (pin "A") (pinfunction "A_A") (pintype "input"))
      (node (ref "IC-IP5305") (pin "LED3") (pinfunction "4_LED3") (pintype "output"))
    )
    (net (code "31") (name "Net-(IC-IP5305-5)") (class "Default")
      (node (ref "IC-IP5305") (pin "KEY") (pinfunction "5_KEY") (pintype "bidirectional"))
      (node (ref "R17") (pin "1") (pinfunction "1_1") (pintype "passive"))
      (node (ref "R3") (pin "1") (pinfunction "1_1") (pintype "passive"))
    )
    (net (code "32") (name "Net-(IC-IP5305-6)") (class "Default")
      (node (ref "C25") (pin "1") (pinfunction "1_1") (pintype "passive"))
      (node (ref "IC-IP5305") (pin "BAT") (pinfunction "6_BAT") (pintype "bidirectional"))
      (node (ref "J3") (pin "2") (pinfunction "2_2") (pintype "passive"))
      (node (ref "L1") (pin "1") (pinfunction "1_1") (pintype "passive"))
    )
    (net (code "33") (name "Net-(IC-IP5305-7)") (class "Default")
      (node (ref "IC-IP5305") (pin "SW") (pinfunction "7_SW") (pintype "bidirectional"))
      (node (ref "L1") (pin "2") (pinfunction "2_2") (pintype "passive"))
    )
    (net (code "34") (name "Net-(IC-IP5305-8)") (class "Default")
      (node (ref "C23") (pin "2") (pinfunction "2_2") (pintype "passive"))
      (node (ref "C24") (pin "2") (pinfunction "2_2") (pintype "passive"))
      (node (ref "IC-IP5305") (pin "VOUT") (pinfunction "8_VOUT") (pintype "bidirectional"))
      (node (ref "RESETTABLE_FUSE") (pin "1") (pinfunction "1_1") (pintype "passive"))
    )
    (net (code "35") (name "Net-(IC3-REF)") (class "Default")
      (node (ref "IC3") (pin "6") (pinfunction "REF_6") (pintype "bidirectional"))
      (node (ref "R6") (pin "1") (pinfunction "1_1") (pintype "passive"))
    )
    (net (code "36") (name "Net-(IC3-RESET#)") (class "Default")
      (node (ref "IC3") (pin "14") (pinfunction "RESET#_14") (pintype "bidirectional"))
      (node (ref "R5") (pin "2") (pinfunction "2_2") (pintype "passive"))
    )
    (net (code "37") (name "Net-(IC4-DO)") (class "Default")
      (node (ref "IC4") (pin "1") (pinfunction "DO_1") (pintype "bidirectional"))
      (node (ref "R10") (pin "1") (pinfunction "1_1") (pintype "passive"))
      (node (ref "R9") (pin "1") (pinfunction "1_1") (pintype "passive"))
    )
    (net (code "38") (name "Net-(KEYLED-PadA)") (class "Default")
      (node (ref "KEYLED") (pin "A") (pinfunction "A_A") (pintype "input"))
      (node (ref "R3") (pin "2") (pinfunction "2_2") (pintype "passive"))
    )
    (net (code "39") (name "Net-(R11-Pad1)") (class "Default")
      (node (ref "R11") (pin "1") (pinfunction "1_1") (pintype "passive"))
      (node (ref "RX-LED") (pin "A") (pinfunction "A_A") (pintype "input"))
    )
    (net (code "40") (name "Net-(R12-Pad1)") (class "Default")
      (node (ref "R12") (pin "1") (pinfunction "1_1") (pintype "passive"))
      (node (ref "TX-LED") (pin "A") (pinfunction "A_A") (pintype "input"))
    )
    (net (code "41") (name "Net-(R13-Pad1)") (class "Default")
      (node (ref "R13") (pin "1") (pinfunction "1_1") (pintype "passive"))
      (node (ref "U$1") (pin "7") (pinfunction "7_7") (pintype "passive"))
    )
    (net (code "42") (name "Net-(R14-Pad1)") (class "Default")
      (node (ref "R14") (pin "1") (pinfunction "1_1") (pintype "passive"))
      (node (ref "U$1") (pin "9") (pinfunction "9_9") (pintype "passive"))
    )
    (net (code "43") (name "Net-(U$5-C)") (class "Default")
      (node (ref "R17") (pin "2") (pinfunction "2_2") (pintype "passive"))
      (node (ref "U$5") (pin "P$2") (pinfunction "C_P$2") (pintype "passive"))
    )
    (net (code "44") (name "Net-(U$10-LED)") (class "Default")
      (node (ref "C34") (pin "1") (pinfunction "1_1") (pintype "passive"))
      (node (ref "R18") (pin "2") (pinfunction "2_2") (pintype "passive"))
      (node (ref "U$10") (pin "8") (pinfunction "LED_8") (pintype "bidirectional"))
    )
    (net (code "45") (name "Net-(U$10-RESET)") (class "Default")
      (node (ref "C2") (pin "1") (pinfunction "1_1") (pintype "passive"))
      (node (ref "R15") (pin "2") (pinfunction "2_2") (pintype "passive"))
      (node (ref "U$10") (pin "4") (pinfunction "RESET_4") (pintype "bidirectional"))
    )
    (net (code "46") (name "OSCI") (class "Default")
      (node (ref "C6") (pin "1") (pinfunction "1_1") (pintype "passive"))
      (node (ref "IC3") (pin "2") (pinfunction "OSCI_2") (pintype "bidirectional"))
      (node (ref "Y1") (pin "2") (pinfunction "2_2") (pintype "bidirectional"))
    )
    (net (code "47") (name "OSCO") (class "Default")
      (node (ref "C7") (pin "1") (pinfunction "1_1") (pintype "passive"))
      (node (ref "IC3") (pin "3") (pinfunction "OSCO_3") (pintype "bidirectional"))
      (node (ref "Y1") (pin "1") (pinfunction "1_1") (pintype "bidirectional"))
    )
    (net (code "48") (name "PAIR_RX") (class "Default")
      (node (ref "J1") (pin "2") (pinfunction "2_2") (pintype "passive"))
      (node (ref "U2") (pin "6") (pinfunction "IO34_6") (pintype "bidirectional"))
    )
    (net (code "49") (name "PAIR_TX") (class "Default")
      (node (ref "J1") (pin "3") (pinfunction "3_3") (pintype "passive"))
      (node (ref "U2") (pin "10") (pinfunction "IO25_10") (pintype "bidirectional"))
    )
    (net (code "50") (name "PROG_RX") (class "Default")
      (node (ref "J4") (pin "4") (pinfunction "4_4") (pintype "passive"))
      (node (ref "R14") (pin "2") (pinfunction "2_2") (pintype "passive"))
      (node (ref "U2") (pin "34") (pinfunction "RXD0_34") (pintype "bidirectional"))
    )
    (net (code "51") (name "PROG_TX") (class "Default")
      (node (ref "J4") (pin "5") (pinfunction "5_5") (pintype "passive"))
      (node (ref "R13") (pin "2") (pinfunction "2_2") (pintype "passive"))
      (node (ref "U2") (pin "35") (pinfunction "TXD0_35") (pintype "bidirectional"))
    )
    (net (code "52") (name "PWREN") (class "Default")
      (node (ref "IC3") (pin "60") (pinfunction "PWREN#_60") (pintype "bidirectional"))
      (node (ref "U$1") (pin "1") (pinfunction "1_1") (pintype "passive"))
    )
    (net (code "53") (name "PWRSAV") (class "Default")
      (node (ref "IC3") (pin "59") (pinfunction "BCBUS7_59") (pintype "bidirectional"))
      (node (ref "R16") (pin "2") (pinfunction "2_2") (pintype "passive"))
      (node (ref "R22") (pin "2") (pinfunction "2_2") (pintype "passive"))
    )
    (net (code "54") (name "RXD_LED") (class "Default")
      (node (ref "IC3") (pin "54") (pinfunction "BCBUS3_54") (pintype "bidirectional"))
      (node (ref "RX-LED") (pin "C") (pinfunction "C_C") (pintype "output"))
    )
    (net (code "55") (name "RXD_SPI_PROM_MOSI") (class "Default")
      (node (ref "IC3") (pin "39") (pinfunction "BDBUS1_39") (pintype "bidirectional"))
      (node (ref "U$1") (pin "8") (pinfunction "8_8") (pintype "passive"))
    )
    (net (code "56") (name "SCL") (class "Default")
      (node (ref "R20") (pin "1") (pinfunction "1_1") (pintype "passive"))
      (node (ref "U$4") (pin "SCL") (pinfunction "SCL_SCL") (pintype "bidirectional"))
      (node (ref "U2") (pin "36") (pinfunction "IO22_36") (pintype "bidirectional"))
    )
    (net (code "57") (name "SCL-2") (class "Default")
      (node (ref "R28") (pin "2") (pinfunction "2_2") (pintype "passive"))
      (node (ref "TOP-BOT-CONNECTOR") (pin "4") (pinfunction "4_4") (pintype "passive"))
      (node (ref "U2") (pin "24") (pinfunction "IO2_24") (pintype "bidirectional"))
    )
    (net (code "58") (name "SDA") (class "Default")
      (node (ref "R19") (pin "2") (pinfunction "2_2") (pintype "passive"))
      (node (ref "U$4") (pin "SDA") (pinfunction "SDA_SDA") (pintype "bidirectional"))
      (node (ref "U2") (pin "33") (pinfunction "IO21_33") (pintype "bidirectional"))
    )
    (net (code "59") (name "SDA-2") (class "Default")
      (node (ref "R29") (pin "2") (pinfunction "2_2") (pintype "passive"))
      (node (ref "TOP-BOT-CONNECTOR") (pin "6") (pinfunction "6_6") (pintype "passive"))
      (node (ref "U2") (pin "27") (pinfunction "IO16_27") (pintype "bidirectional"))
    )
    (net (code "60") (name "SD_CS") (class "Default")
      (node (ref "U$10") (pin "15") (pinfunction "SD_CS_15") (pintype "bidirectional"))
      (node (ref "U2") (pin "29") (pinfunction "IO5_29") (pintype "bidirectional"))
    )
    (net (code "61") (name "SPI_PROM_CS") (class "Default")
      (node (ref "IC3") (pin "41") (pinfunction "BDBUS3_41") (pintype "bidirectional"))
      (node (ref "U$1") (pin "4") (pinfunction "4_4") (pintype "passive"))
    )
    (net (code "62") (name "SPI_PROM_MISO") (class "Default")
      (node (ref "IC3") (pin "40") (pinfunction "BDBUS2_40") (pintype "bidirectional"))
      (node (ref "U$1") (pin "6") (pinfunction "6_6") (pintype "passive"))
    )
    (net (code "63") (name "SUSPEND") (class "Default")
      (node (ref "IC3") (pin "36") (pinfunction "SUSPEND__#_36") (pintype "bidirectional"))
      (node (ref "U$1") (pin "3") (pinfunction "3_3") (pintype "passive"))
    )
    (net (code "64") (name "SVN") (class "Default")
      (node (ref "R21") (pin "1") (pinfunction "1_1") (pintype "passive"))
      (node (ref "TOP-BOT-CONNECTOR") (pin "3") (pinfunction "3_3") (pintype "passive"))
      (node (ref "U2") (pin "5") (pinfunction "SENSOR_VN_5") (pintype "bidirectional"))
    )
    (net (code "65") (name "SVP") (class "Default")
      (node (ref "R27") (pin "1") (pinfunction "1_1") (pintype "passive"))
      (node (ref "TOP-BOT-CONNECTOR") (pin "5") (pinfunction "5_5") (pintype "passive"))
      (node (ref "U2") (pin "4") (pinfunction "SENSOR_VP_4") (pintype "bidirectional"))
    )
    (net (code "66") (name "TOUCH_CLK") (class "Default")
      (node (ref "U$10") (pin "10") (pinfunction "T_CLK_10") (pintype "bidirectional"))
      (node (ref "U2") (pin "11") (pinfunction "IO26_11") (pintype "bidirectional"))
    )
    (net (code "67") (name "TOUCH_CS") (class "Default")
      (node (ref "U$10") (pin "11") (pinfunction "T_CS_11") (pintype "bidirectional"))
      (node (ref "U2") (pin "12") (pinfunction "IO27_12") (pintype "bidirectional"))
    )
    (net (code "68") (name "TOUCH_DATA_IN") (class "Default")
      (node (ref "U$10") (pin "12") (pinfunction "T_DIN_12") (pintype "bidirectional"))
      (node (ref "U2") (pin "9") (pinfunction "IO33_9") (pintype "bidirectional"))
    )
    (net (code "69") (name "TOUCH_DATA_OUT") (class "Default")
      (node (ref "U$10") (pin "13") (pinfunction "T_DO_13") (pintype "bidirectional"))
      (node (ref "U2") (pin "7") (pinfunction "IO35_7") (pintype "bidirectional"))
    )
    (net (code "70") (name "TOUCH_IRQ") (class "Default")
      (node (ref "U$10") (pin "14") (pinfunction "T_IRQ_14") (pintype "bidirectional"))
      (node (ref "U2") (pin "8") (pinfunction "IO32_8") (pintype "bidirectional"))
    )
    (net (code "71") (name "TXD_LED") (class "Default")
      (node (ref "IC3") (pin "55") (pinfunction "BCBUS4_55") (pintype "bidirectional"))
      (node (ref "TX-LED") (pin "C") (pinfunction "C_C") (pintype "output"))
    )
    (net (code "72") (name "TXD_SPI_PROM_CLK") (class "Default")
      (node (ref "IC3") (pin "38") (pinfunction "BDBUS0_38") (pintype "bidirectional"))
      (node (ref "U$1") (pin "10") (pinfunction "10_10") (pintype "passive"))
    )
    (net (code "73") (name "USB_DM") (class "Default")
      (node (ref "IC3") (pin "7") (pinfunction "DM_7") (pintype "bidirectional"))
      (node (ref "U$2") (pin "P1") (pinfunction "P1_P1") (pintype "bidirectional"))
      (node (ref "U$3") (pin "D-") (pinfunction "D-_D-") (pintype "bidirectional"))
    )
    (net (code "74") (name "USB_DP") (class "Default")
      (node (ref "IC3") (pin "8") (pinfunction "DP_8") (pintype "bidirectional"))
      (node (ref "U$2") (pin "P6") (pinfunction "P6_P6") (pintype "bidirectional"))
      (node (ref "U$3") (pin "D+") (pinfunction "D+_D+") (pintype "bidirectional"))
    )
    (net (code "75") (name "VBAT") (class "Default")
      (node (ref "C4") (pin "1") (pinfunction "1_1") (pintype "passive"))
      (node (ref "IC2") (pin "4") (pinfunction "VIN_4") (pintype "bidirectional"))
      (node (ref "PWR") (pin "A1") (pinfunction "NO_A1") (pintype "bidirectional"))
      (node (ref "RESETTABLE_FUSE") (pin "2") (pinfunction "2_2") (pintype "passive"))
    )
    (net (code "76") (name "VCC") (class "Default")
      (node (ref "C1") (pin "1") (pinfunction "1_1") (pintype "passive"))
      (node (ref "C11") (pin "1") (pinfunction "1_1") (pintype "passive"))
      (node (ref "C14") (pin "1") (pinfunction "1_1") (pintype "passive"))
      (node (ref "C15") (pin "1") (pinfunction "1_1") (pintype "passive"))
      (node (ref "C16") (pin "1") (pinfunction "1_1") (pintype "passive"))
      (node (ref "C3") (pin "1") (pinfunction "1_1") (pintype "passive"))
      (node (ref "C35") (pin "1") (pinfunction "1_1") (pintype "passive"))
      (node (ref "C5") (pin "1") (pinfunction "1_1") (pintype "passive"))
      (node (ref "C8") (pin "1") (pinfunction "1_1") (pintype "passive"))
      (node (ref "EMIFILTER1") (pin "1") (pinfunction "IN/OUT_1") (pintype "bidirectional"))
      (node (ref "EMIFILTER2") (pin "1") (pinfunction "IN/OUT_1") (pintype "bidirectional"))
      (node (ref "IC2") (pin "1") (pinfunction "VOUT_1") (pintype "bidirectional"))
      (node (ref "IC3") (pin "20") (pinfunction "VCCIO_1_20") (pintype "bidirectional"))
      (node (ref "IC3") (pin "31") (pinfunction "VCCIO_2_31") (pintype "bidirectional"))
      (node (ref "IC3") (pin "42") (pinfunction "VCCIO_3_42") (pintype "bidirectional"))
      (node (ref "IC3") (pin "50") (pinfunction "VREGIN_50") (pintype "bidirectional"))
      (node (ref "IC3") (pin "56") (pinfunction "VCCIO_4_56") (pintype "bidirectional"))
      (node (ref "IC4") (pin "6") (pinfunction "VCC_6") (pintype "power_in"))
      (node (ref "J4") (pin "6") (pinfunction "6_6") (pintype "passive"))
      (node (ref "R1") (pin "2") (pinfunction "2_2") (pintype "passive"))
      (node (ref "R11") (pin "2") (pinfunction "2_2") (pintype "passive"))
      (node (ref "R12") (pin "2") (pinfunction "2_2") (pintype "passive"))
      (node (ref "R15") (pin "1") (pinfunction "1_1") (pintype "passive"))
      (node (ref "R18") (pin "1") (pinfunction "1_1") (pintype "passive"))
      (node (ref "R19") (pin "1") (pinfunction "1_1") (pintype "passive"))
      (node (ref "R20") (pin "2") (pinfunction "2_2") (pintype "passive"))
      (node (ref "R21") (pin "2") (pinfunction "2_2") (pintype "passive"))
      (node (ref "R27") (pin "2") (pinfunction "2_2") (pintype "passive"))
      (node (ref "R28") (pin "1") (pinfunction "1_1") (pintype "passive"))
      (node (ref "R29") (pin "1") (pinfunction "1_1") (pintype "passive"))
      (node (ref "R4") (pin "2") (pinfunction "2_2") (pintype "passive"))
      (node (ref "R5") (pin "1") (pinfunction "1_1") (pintype "passive"))
      (node (ref "R7") (pin "2") (pinfunction "2_2") (pintype "passive"))
      (node (ref "R8") (pin "1") (pinfunction "1_1") (pintype "passive"))
      (node (ref "R9") (pin "2") (pinfunction "2_2") (pintype "passive"))
      (node (ref "TOP-BOT-CONNECTOR") (pin "2") (pinfunction "2_2") (pintype "passive"))
      (node (ref "U$1") (pin "12") (pinfunction "12_12") (pintype "passive"))
      (node (ref "U$10") (pin "1") (pinfunction "VCC_1") (pintype "power_in"))
      (node (ref "U$4") (pin "VCC") (pinfunction "VCC_VCC") (pintype "power_in"))
      (node (ref "U2") (pin "2") (pinfunction "3V3_2") (pintype "bidirectional"))
    )
    (net (code "77") (name "VCC1.8") (class "Default")
      (node (ref "C10") (pin "1") (pinfunction "1_1") (pintype "passive"))
      (node (ref "C12") (pin "1") (pinfunction "1_1") (pintype "passive"))
      (node (ref "C17") (pin "1") (pinfunction "1_1") (pintype "passive"))
      (node (ref "C9") (pin "1") (pinfunction "1_1") (pintype "passive"))
      (node (ref "IC3") (pin "12") (pinfunction "VCORE_1_12") (pintype "bidirectional"))
      (node (ref "IC3") (pin "37") (pinfunction "VCORE_2_37") (pintype "bidirectional"))
      (node (ref "IC3") (pin "49") (pinfunction "VREGOUT_49") (pintype "bidirectional"))
      (node (ref "IC3") (pin "64") (pinfunction "VCORE_3_64") (pintype "bidirectional"))
    )
    (net (code "78") (name "VCC5V") (class "Default")
      (node (ref "C13") (pin "2") (pinfunction "2_2") (pintype "passive"))
      (node (ref "IC-IP5305") (pin "VIN") (pinfunction "1_VIN") (pintype "power_in"))
      (node (ref "R16") (pin "1") (pinfunction "1_1") (pintype "passive"))
      (node (ref "R2") (pin "1") (pinfunction "1_1") (pintype "passive"))
      (node (ref "U$3") (pin "+5V") (pinfunction "+5V_+5V") (pintype "bidirectional"))
    )
    (net (code "79") (name "unconnected-(IC2-ADJ-Pad8)") (class "Default")
      (node (ref "IC2") (pin "8") (pinfunction "ADJ_8") (pintype "bidirectional"))
    )
    (net (code "80") (name "unconnected-(IC3-ACBUS0-Pad26)") (class "Default")
      (node (ref "IC3") (pin "26") (pinfunction "ACBUS0_26") (pintype "bidirectional"))
    )
    (net (code "81") (name "unconnected-(IC3-ACBUS1-Pad27)") (class "Default")
      (node (ref "IC3") (pin "27") (pinfunction "ACBUS1_27") (pintype "bidirectional"))
    )
    (net (code "82") (name "unconnected-(IC3-ACBUS2-Pad28)") (class "Default")
      (node (ref "IC3") (pin "28") (pinfunction "ACBUS2_28") (pintype "bidirectional"))
    )
    (net (code "83") (name "unconnected-(IC3-ACBUS3-Pad29)") (class "Default")
      (node (ref "IC3") (pin "29") (pinfunction "ACBUS3_29") (pintype "bidirectional"))
    )
    (net (code "84") (name "unconnected-(IC3-ACBUS4-Pad30)") (class "Default")
      (node (ref "IC3") (pin "30") (pinfunction "ACBUS4_30") (pintype "bidirectional"))
    )
    (net (code "85") (name "unconnected-(IC3-ACBUS5-Pad32)") (class "Default")
      (node (ref "IC3") (pin "32") (pinfunction "ACBUS5_32") (pintype "bidirectional"))
    )
    (net (code "86") (name "unconnected-(IC3-ACBUS6-Pad33)") (class "Default")
      (node (ref "IC3") (pin "33") (pinfunction "ACBUS6_33") (pintype "bidirectional"))
    )
    (net (code "87") (name "unconnected-(IC3-ACBUS7-Pad34)") (class "Default")
      (node (ref "IC3") (pin "34") (pinfunction "ACBUS7_34") (pintype "bidirectional"))
    )
    (net (code "88") (name "unconnected-(IC3-ADBUS4-Pad21)") (class "Default")
      (node (ref "IC3") (pin "21") (pinfunction "ADBUS4_21") (pintype "bidirectional"))
    )
    (net (code "89") (name "unconnected-(IC3-ADBUS5-Pad22)") (class "Default")
      (node (ref "IC3") (pin "22") (pinfunction "ADBUS5_22") (pintype "bidirectional"))
    )
    (net (code "90") (name "unconnected-(IC3-ADBUS6-Pad23)") (class "Default")
      (node (ref "IC3") (pin "23") (pinfunction "ADBUS6_23") (pintype "bidirectional"))
    )
    (net (code "91") (name "unconnected-(IC3-ADBUS7-Pad24)") (class "Default")
      (node (ref "IC3") (pin "24") (pinfunction "ADBUS7_24") (pintype "bidirectional"))
    )
    (net (code "92") (name "unconnected-(IC3-BCBUS0-Pad48)") (class "Default")
      (node (ref "IC3") (pin "48") (pinfunction "BCBUS0_48") (pintype "bidirectional"))
    )
    (net (code "93") (name "unconnected-(IC3-BCBUS1-Pad52)") (class "Default")
      (node (ref "IC3") (pin "52") (pinfunction "BCBUS1_52") (pintype "bidirectional"))
    )
    (net (code "94") (name "unconnected-(IC3-BCBUS2-Pad53)") (class "Default")
      (node (ref "IC3") (pin "53") (pinfunction "BCBUS2_53") (pintype "bidirectional"))
    )
    (net (code "95") (name "unconnected-(IC3-BCBUS5-Pad57)") (class "Default")
      (node (ref "IC3") (pin "57") (pinfunction "BCBUS5_57") (pintype "bidirectional"))
    )
    (net (code "96") (name "unconnected-(IC3-BCBUS6-Pad58)") (class "Default")
      (node (ref "IC3") (pin "58") (pinfunction "BCBUS6_58") (pintype "bidirectional"))
    )
    (net (code "97") (name "unconnected-(IC3-BDBUS4-Pad43)") (class "Default")
      (node (ref "IC3") (pin "43") (pinfunction "BDBUS4_43") (pintype "bidirectional"))
    )
    (net (code "98") (name "unconnected-(IC3-BDBUS5-Pad44)") (class "Default")
      (node (ref "IC3") (pin "44") (pinfunction "BDBUS5_44") (pintype "bidirectional"))
    )
    (net (code "99") (name "unconnected-(IC3-BDBUS6-Pad45)") (class "Default")
      (node (ref "IC3") (pin "45") (pinfunction "BDBUS6_45") (pintype "bidirectional"))
    )
    (net (code "100") (name "unconnected-(IC3-BDBUS7-Pad46)") (class "Default")
      (node (ref "IC3") (pin "46") (pinfunction "BDBUS7_46") (pintype "bidirectional"))
    )
    (net (code "101") (name "unconnected-(PWR-PadMP1)") (class "Default")
      (node (ref "PWR") (pin "MP1") (pinfunction "MP1_MP1") (pintype "bidirectional"))
    )
    (net (code "102") (name "unconnected-(PWR-PadMP2)") (class "Default")
      (node (ref "PWR") (pin "MP2") (pinfunction "MP2_MP2") (pintype "bidirectional"))
    )
    (net (code "103") (name "unconnected-(PWR-PadMP3)") (class "Default")
      (node (ref "PWR") (pin "MP3") (pinfunction "MP3_MP3") (pintype "bidirectional"))
    )
    (net (code "104") (name "unconnected-(PWR-PadMP4)") (class "Default")
      (node (ref "PWR") (pin "MP4") (pinfunction "MP4_MP4") (pintype "bidirectional"))
    )
    (net (code "105") (name "unconnected-(TOP-BOT-CONNECTOR-Pad7)") (class "Default")
      (node (ref "TOP-BOT-CONNECTOR") (pin "7") (pinfunction "7_7") (pintype "passive"))
    )
    (net (code "106") (name "unconnected-(TOP-BOT-CONNECTOR-Pad8)") (class "Default")
      (node (ref "TOP-BOT-CONNECTOR") (pin "8") (pinfunction "8_8") (pintype "passive"))
    )
    (net (code "107") (name "unconnected-(TOP-BOT-CONNECTOR-Pad9)") (class "Default")
      (node (ref "TOP-BOT-CONNECTOR") (pin "9") (pinfunction "9_9") (pintype "passive"))
    )
    (net (code "108") (name "unconnected-(TOP-BOT-CONNECTOR-Pad10)") (class "Default")
      (node (ref "TOP-BOT-CONNECTOR") (pin "10") (pinfunction "10_10") (pintype "passive"))
    )
    (net (code "109") (name "unconnected-(U$1-Pad5)") (class "Default")
      (node (ref "U$1") (pin "5") (pinfunction "5_5") (pintype "passive"))
    )
    (net (code "110") (name "unconnected-(U$1-Pad11)") (class "Default")
      (node (ref "U$1") (pin "11") (pinfunction "11_11") (pintype "passive"))
    )
    (net (code "111") (name "unconnected-(U$2-PadP3)") (class "Default")
      (node (ref "U$2") (pin "P3") (pinfunction "P3_P3") (pintype "bidirectional"))
    )
    (net (code "112") (name "unconnected-(U$2-PadP4)") (class "Default")
      (node (ref "U$2") (pin "P4") (pinfunction "P4_P4") (pintype "bidirectional"))
    )
    (net (code "113") (name "unconnected-(U$2-PadP5)") (class "Default")
      (node (ref "U$2") (pin "P5") (pinfunction "P5_P5") (pintype "bidirectional"))
    )
    (net (code "114") (name "unconnected-(U$3-PadID)") (class "Default")
      (node (ref "U$3") (pin "ID") (pinfunction "ID_ID") (pintype "bidirectional"))
    )
    (net (code "115") (name "unconnected-(U$4-NC_1-PadNC1)") (class "Default")
      (node (ref "U$4") (pin "NC1") (pinfunction "NC_1_NC1") (pintype "no_connect"))
    )
    (net (code "116") (name "unconnected-(U$4-NC_2-PadNC2)") (class "Default")
      (node (ref "U$4") (pin "NC2") (pinfunction "NC_2_NC2") (pintype "no_connect"))
    )
    (net (code "117") (name "unconnected-(U$4-NC_3-PadNC3)") (class "Default")
      (node (ref "U$4") (pin "NC3") (pinfunction "NC_3_NC3") (pintype "no_connect"))
    )
    (net (code "118") (name "unconnected-(U$4-NC_4-PadNC4)") (class "Default")
      (node (ref "U$4") (pin "NC4") (pinfunction "NC_4_NC4") (pintype "no_connect"))
    )
    (net (code "119") (name "unconnected-(U2-CLK-Pad20)") (class "Default")
      (node (ref "U2") (pin "20") (pinfunction "CLK_20") (pintype "bidirectional"))
    )
    (net (code "120") (name "unconnected-(U2-CMD-Pad19)") (class "Default")
      (node (ref "U2") (pin "19") (pinfunction "CMD_19") (pintype "bidirectional"))
    )
    (net (code "121") (name "unconnected-(U2-NC-Pad32)") (class "Default")
      (node (ref "U2") (pin "32") (pinfunction "NC_32") (pintype "bidirectional"))
    )
    (net (code "122") (name "unconnected-(U2-SD1-Pad22)") (class "Default")
      (node (ref "U2") (pin "22") (pinfunction "SD1_22") (pintype "bidirectional"))
    )
    (net (code "123") (name "unconnected-(U2-SD2-Pad17)") (class "Default")
      (node (ref "U2") (pin "17") (pinfunction "SD2_17") (pintype "bidirectional"))
    )
    (net (code "124") (name "unconnected-(U2-SD3-Pad18)") (class "Default")
      (node (ref "U2") (pin "18") (pinfunction "SD3_18") (pintype "bidirectional"))
    )
    (net (code "125") (name "unconnected-(U2-SDO-Pad21)") (class "Default")
      (node (ref "U2") (pin "21") (pinfunction "SDO_21") (pintype "bidirectional"))
    )
  )
)
